# HABduino1_1.net
KiCad netlist of a schematic drawn in EAGLE
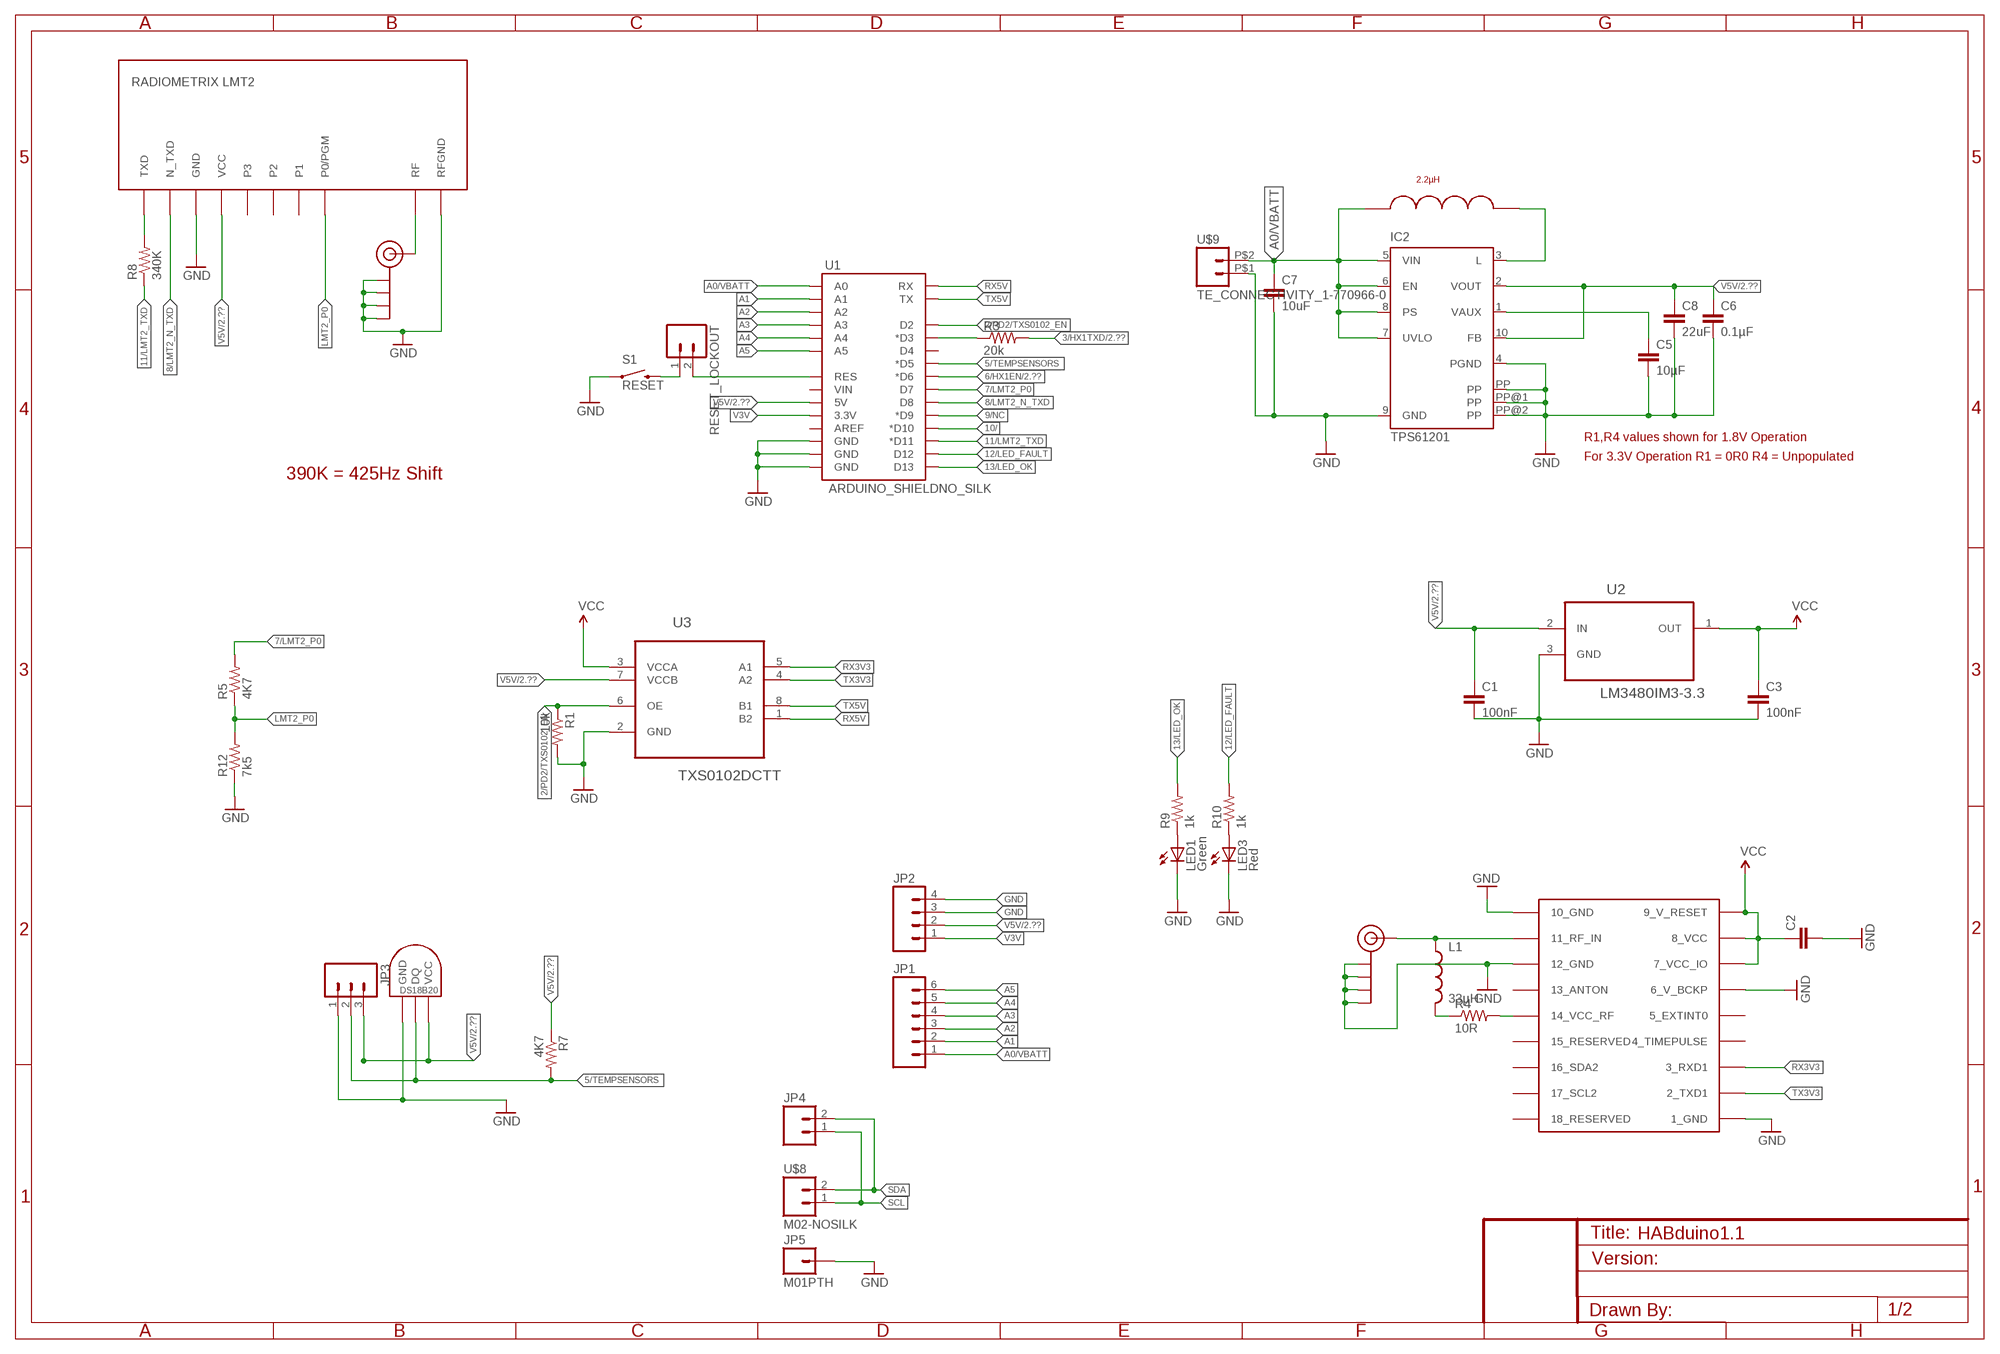
[diagram p0: schematic, sheet 1]
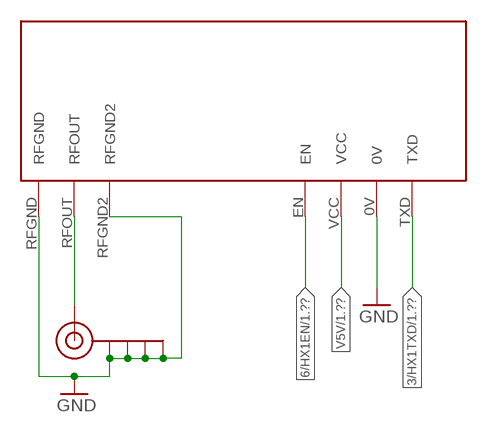
[diagram p1: schematic, sheet 2]

(export (version "E")
  (design (tool "Eeschema 10.0.6"))
  (components
    (comp (ref "J$3")
      (value "SMA_EDGE")
      (footprint "eagle-import:SMA-EDGE")
      (libsource (lib "eagle-import") (part "SMA_EDGE"))
    )
    (comp (ref "U$7")
      (value "RADIOMETRIX-HX1")
      (footprint "eagle-import:RADIOMETRIX-HX1")
      (libsource (lib "eagle-import") (part "RADIOMETRIX-HX1"))
    )
    (comp (ref "C1")
      (value "100nF")
      (footprint "eagle-import:0603-CAP")
      (libsource (lib "eagle-import") (part "CAP0603-CAP"))
    )
    (comp (ref "C2")
      (value "CAP0603-CAP")
      (footprint "eagle-import:0603-CAP")
      (libsource (lib "eagle-import") (part "CAP0603-CAP"))
    )
    (comp (ref "C3")
      (value "100nF")
      (footprint "eagle-import:0603-CAP")
      (libsource (lib "eagle-import") (part "CAP0603-CAP"))
    )
    (comp (ref "C5")
      (value "10µF")
      (footprint "eagle-import:0603-CAP")
      (libsource (lib "eagle-import") (part "CAP0603-CAP"))
    )
    (comp (ref "C6")
      (value "0.1µF")
      (footprint "eagle-import:0603-CAP")
      (libsource (lib "eagle-import") (part "CAP0603-CAP"))
    )
    (comp (ref "C7")
      (value "10uF")
      (footprint "eagle-import:1206")
      (libsource (lib "eagle-import") (part "CAP1206"))
    )
    (comp (ref "C8")
      (value "22uF")
      (footprint "eagle-import:1206")
      (libsource (lib "eagle-import") (part "CAP1206"))
    )
    (comp (ref "IC2")
      (value "TPS61201")
      (footprint "eagle-import:S-PDSO-N10")
      (fields (field (name "MPN") "TPS61201DRCT"))
      (libsource (lib "eagle-import") (part "TPS61201"))
    )
    (comp (ref "J$1")
      (value "SMA_EDGE")
      (footprint "eagle-import:SMA-EDGE")
      (libsource (lib "eagle-import") (part "SMA_EDGE"))
    )
    (comp (ref "J$2")
      (value "SMA_EDGE")
      (footprint "eagle-import:SMA-EDGE")
      (libsource (lib "eagle-import") (part "SMA_EDGE"))
    )
    (comp (ref "JP1")
      (value "M06SIP")
      (footprint "eagle-import:1X06")
      (libsource (lib "eagle-import") (part "M06SIP"))
    )
    (comp (ref "JP2")
      (value "M04PTH")
      (footprint "eagle-import:1X04")
      (libsource (lib "eagle-import") (part "M04PTH"))
    )
    (comp (ref "JP3")
      (value "M03PTH")
      (footprint "eagle-import:1X03")
      (libsource (lib "eagle-import") (part "M03PTH"))
    )
    (comp (ref "JP4")
      (value "M02PTH")
      (footprint "eagle-import:1X02")
      (libsource (lib "eagle-import") (part "M02PTH"))
    )
    (comp (ref "JP5")
      (value "M01PTH")
      (footprint "eagle-import:1X01")
      (libsource (lib "eagle-import") (part "M01PTH"))
    )
    (comp (ref "L1")
      (value "33µH")
      (footprint "eagle-import:0603")
      (libsource (lib "eagle-import") (part "INDUCTOR0603"))
    )
    (comp (ref "LED1")
      (value "Green")
      (footprint "eagle-import:LED-0603")
      (libsource (lib "eagle-import") (part "LED0603"))
    )
    (comp (ref "LED3")
      (value "Red")
      (footprint "eagle-import:LED-0603")
      (libsource (lib "eagle-import") (part "LED0603"))
    )
    (comp (ref "R1")
      (value "10k")
      (footprint "eagle-import:0603-RES")
      (libsource (lib "eagle-import") (part "RESISTOR0603-RES"))
    )
    (comp (ref "R3")
      (value "20k")
      (footprint "eagle-import:0603-RES")
      (libsource (lib "eagle-import") (part "RESISTOR0603-RES"))
    )
    (comp (ref "R4")
      (value "10R")
      (footprint "eagle-import:0603-RES")
      (libsource (lib "eagle-import") (part "RESISTOR0603-RES"))
    )
    (comp (ref "R5")
      (value "4K7")
      (footprint "eagle-import:0603-RES")
      (libsource (lib "eagle-import") (part "RESISTOR0603-RES"))
    )
    (comp (ref "R7")
      (value "4K7")
      (footprint "eagle-import:0603-RES")
      (libsource (lib "eagle-import") (part "RESISTOR0603-RES"))
    )
    (comp (ref "R8")
      (value "340K")
      (footprint "eagle-import:0603-RES")
      (libsource (lib "eagle-import") (part "RESISTOR0603-RES"))
    )
    (comp (ref "R9")
      (value "1k")
      (footprint "eagle-import:0603-RES")
      (libsource (lib "eagle-import") (part "RESISTOR0603-RES"))
    )
    (comp (ref "R10")
      (value "1k")
      (footprint "eagle-import:0603-RES")
      (libsource (lib "eagle-import") (part "RESISTOR0603-RES"))
    )
    (comp (ref "R12")
      (value "7k5")
      (footprint "eagle-import:0603-RES")
      (libsource (lib "eagle-import") (part "RESISTOR0603-RES"))
    )
    (comp (ref "RESET_LOCKOUT")
      (value "M02PTH")
      (footprint "eagle-import:1X02")
      (libsource (lib "eagle-import") (part "M02PTH"))
    )
    (comp (ref "S1")
      (value "RESET")
      (footprint "eagle-import:TACTILE_SWITCH_TALL")
      (libsource (lib "eagle-import") (part "SWITCH-MOMENTARY-2"))
    )
    (comp (ref "TEMPINT")
      (value "DS1821")
      (footprint "eagle-import:DS1820")
      (libsource (lib "eagle-import") (part "DS1820TO92"))
    )
    (comp (ref "U$1")
      (value "UBLOX_MAX-6")
      (footprint "eagle-import:UBLOX_MAX-6")
      (libsource (lib "eagle-import") (part "UBLOX_MAX-6"))
    )
    (comp (ref "U$2")
      (value "RADIOMETRIX_LMT2")
      (footprint "eagle-import:RADIOMETRIX-LMT2")
      (libsource (lib "eagle-import") (part "RADIOMETRIX_LMT2"))
    )
    (comp (ref "U$8")
      (value "M02-NOSILK")
      (footprint "eagle-import:M02-NOSILK")
      (libsource (lib "eagle-import") (part "M02-NOSILK"))
    )
    (comp (ref "U$9")
      (value "TE_CONNECTIVITY_1-770966-0")
      (footprint "eagle-import:TE_CONNECTIVITY_1-770966-0")
      (libsource (lib "eagle-import") (part "TE_CONNECTIVITY_1-770966-0"))
    )
    (comp (ref "U$10")
      (value "2.2µH")
      (footprint "eagle-import:COILCRAFT_LPS4018")
      (libsource (lib "eagle-import") (part "COILCRAFT_LPS4018"))
    )
    (comp (ref "U1")
      (value "ARDUINO_SHIELDNO_SILK")
      (footprint "eagle-import:DUEMILANOVE_VIAS")
      (libsource (lib "eagle-import") (part "ARDUINO_SHIELDNO_SILK"))
    )
    (comp (ref "U2")
      (value "LM3480IM3-3.3")
      (footprint "eagle-import:SOT95P251X112-3N")
      (libsource (lib "eagle-import") (part "LM3480IM3-3.3"))
    )
    (comp (ref "U3")
      (value "TXS0102DCTT")
      (footprint "eagle-import:SOP65P400X130-8N")
      (libsource (lib "eagle-import") (part "TXS0102DCTT"))
    )
  )
  (nets
    (net (code "1") (name "2{slash}PD2{slash}TXS0102_EN") (class "Default")
      (node (ref "R1") (pin "1") (pinfunction "1_1") (pintype "passive"))
      (node (ref "U1") (pin "D2") (pinfunction "D2_D2") (pintype "bidirectional"))
      (node (ref "U3") (pin "6") (pinfunction "OE_6") (pintype "input"))
    )
    (net (code "2") (name "3{slash}HX1TXD") (class "Default")
      (node (ref "R3") (pin "2") (pinfunction "2_2") (pintype "passive"))
      (node (ref "U$7") (pin "TXD") (pinfunction "TXD_TXD") (pintype "bidirectional"))
    )
    (net (code "3") (name "5{slash}TEMPSENSORS") (class "Default")
      (node (ref "JP3") (pin "2") (pinfunction "2_2") (pintype "passive"))
      (node (ref "R7") (pin "2") (pinfunction "2_2") (pintype "passive"))
      (node (ref "TEMPINT") (pin "DQ") (pinfunction "DQ_DQ") (pintype "bidirectional"))
      (node (ref "U1") (pin "D5") (pinfunction "*D5_D5") (pintype "bidirectional"))
    )
    (net (code "4") (name "6{slash}HX1EN") (class "Default")
      (node (ref "U$7") (pin "EN") (pinfunction "EN_EN") (pintype "bidirectional"))
      (node (ref "U1") (pin "D6") (pinfunction "*D6_D6") (pintype "bidirectional"))
    )
    (net (code "5") (name "7{slash}LMT2_P0") (class "Default")
      (node (ref "R5") (pin "2") (pinfunction "2_2") (pintype "passive"))
      (node (ref "U1") (pin "D7") (pinfunction "D7_D7") (pintype "bidirectional"))
    )
    (net (code "6") (name "8{slash}LMT2_N_TXD") (class "Default")
      (node (ref "U$2") (pin "N_TXE") (pinfunction "N_TXD_N_TXE") (pintype "bidirectional"))
      (node (ref "U1") (pin "D8") (pinfunction "D8_D8") (pintype "bidirectional"))
    )
    (net (code "7") (name "9{slash}NC") (class "Default")
      (node (ref "U1") (pin "D9") (pinfunction "*D9_D9") (pintype "bidirectional"))
    )
    (net (code "8") (name "10{slash}") (class "Default")
      (node (ref "U1") (pin "D10") (pinfunction "*D10_D10") (pintype "bidirectional"))
    )
    (net (code "9") (name "11{slash}LMT2_TXD") (class "Default")
      (node (ref "R8") (pin "1") (pinfunction "1_1") (pintype "passive"))
      (node (ref "U1") (pin "D11") (pinfunction "*D11_D11") (pintype "bidirectional"))
    )
    (net (code "10") (name "12{slash}LED_FAULT") (class "Default")
      (node (ref "R10") (pin "2") (pinfunction "2_2") (pintype "passive"))
      (node (ref "U1") (pin "D12") (pinfunction "D12_D12") (pintype "bidirectional"))
    )
    (net (code "11") (name "13{slash}LED_OK") (class "Default")
      (node (ref "R9") (pin "2") (pinfunction "2_2") (pintype "passive"))
      (node (ref "U1") (pin "D13") (pinfunction "D13_D13") (pintype "bidirectional"))
    )
    (net (code "12") (name "A0{slash}VBATT") (class "Default")
      (node (ref "C7") (pin "1") (pinfunction "1_1") (pintype "passive"))
      (node (ref "IC2") (pin "5") (pinfunction "VIN_5") (pintype "input"))
      (node (ref "IC2") (pin "6") (pinfunction "EN_6") (pintype "input"))
      (node (ref "IC2") (pin "7") (pinfunction "UVLO_7") (pintype "input"))
      (node (ref "IC2") (pin "8") (pinfunction "PS_8") (pintype "input"))
      (node (ref "JP1") (pin "1") (pinfunction "1_1") (pintype "passive"))
      (node (ref "U$10") (pin "P$1") (pinfunction "P$1_P$1") (pintype "bidirectional"))
      (node (ref "U$9") (pin "P$2") (pinfunction "2_P$2") (pintype "passive"))
      (node (ref "U1") (pin "A0") (pinfunction "A0_A0") (pintype "bidirectional"))
    )
    (net (code "13") (name "A1") (class "Default")
      (node (ref "JP1") (pin "2") (pinfunction "2_2") (pintype "passive"))
      (node (ref "U1") (pin "A1") (pinfunction "A1_A1") (pintype "bidirectional"))
    )
    (net (code "14") (name "A2") (class "Default")
      (node (ref "JP1") (pin "3") (pinfunction "3_3") (pintype "passive"))
      (node (ref "U1") (pin "A2") (pinfunction "A2_A2") (pintype "bidirectional"))
    )
    (net (code "15") (name "A3") (class "Default")
      (node (ref "JP1") (pin "4") (pinfunction "4_4") (pintype "passive"))
      (node (ref "U1") (pin "A3") (pinfunction "A3_A3") (pintype "bidirectional"))
    )
    (net (code "16") (name "A4") (class "Default")
      (node (ref "JP1") (pin "5") (pinfunction "5_5") (pintype "passive"))
      (node (ref "U1") (pin "A4") (pinfunction "A4_A4") (pintype "bidirectional"))
    )
    (net (code "17") (name "A5") (class "Default")
      (node (ref "JP1") (pin "6") (pinfunction "6_6") (pintype "passive"))
      (node (ref "U1") (pin "A5") (pinfunction "A5_A5") (pintype "bidirectional"))
    )
    (net (code "18") (name "GND") (class "Default")
      (node (ref "C1") (pin "2") (pinfunction "2_2") (pintype "passive"))
      (node (ref "C2") (pin "2") (pinfunction "2_2") (pintype "passive"))
      (node (ref "C3") (pin "2") (pinfunction "2_2") (pintype "passive"))
      (node (ref "C5") (pin "2") (pinfunction "2_2") (pintype "passive"))
      (node (ref "C6") (pin "2") (pinfunction "2_2") (pintype "passive"))
      (node (ref "C7") (pin "2") (pinfunction "2_2") (pintype "passive"))
      (node (ref "C8") (pin "2") (pinfunction "2_2") (pintype "passive"))
      (node (ref "IC2") (pin "4") (pinfunction "PGND_4") (pintype "power_in"))
      (node (ref "IC2") (pin "9") (pinfunction "GND_9") (pintype "power_in"))
      (node (ref "IC2") (pin "PP") (pinfunction "PP_PP") (pintype "power_in"))
      (node (ref "IC2") (pin "PP@1") (pinfunction "PP_PP@1") (pintype "power_in"))
      (node (ref "IC2") (pin "PP@2") (pinfunction "PP_PP@2") (pintype "power_in"))
      (node (ref "J$1") (pin "GND@0") (pinfunction "GND_GND@0") (pintype "bidirectional"))
      (node (ref "J$1") (pin "GND@1") (pinfunction "GND_GND@1") (pintype "bidirectional"))
      (node (ref "J$1") (pin "GND@2") (pinfunction "GND_GND@2") (pintype "bidirectional"))
      (node (ref "J$1") (pin "GND@3") (pinfunction "GND_GND@3") (pintype "bidirectional"))
      (node (ref "J$2") (pin "GND@0") (pinfunction "GND_GND@0") (pintype "bidirectional"))
      (node (ref "J$2") (pin "GND@1") (pinfunction "GND_GND@1") (pintype "bidirectional"))
      (node (ref "J$2") (pin "GND@2") (pinfunction "GND_GND@2") (pintype "bidirectional"))
      (node (ref "J$2") (pin "GND@3") (pinfunction "GND_GND@3") (pintype "bidirectional"))
      (node (ref "J$3") (pin "GND@0") (pinfunction "GND_GND@0") (pintype "bidirectional"))
      (node (ref "J$3") (pin "GND@1") (pinfunction "GND_GND@1") (pintype "bidirectional"))
      (node (ref "J$3") (pin "GND@2") (pinfunction "GND_GND@2") (pintype "bidirectional"))
      (node (ref "J$3") (pin "GND@3") (pinfunction "GND_GND@3") (pintype "bidirectional"))
      (node (ref "JP2") (pin "3") (pinfunction "3_3") (pintype "passive"))
      (node (ref "JP2") (pin "4") (pinfunction "4_4") (pintype "passive"))
      (node (ref "JP3") (pin "1") (pinfunction "1_1") (pintype "passive"))
      (node (ref "JP5") (pin "1") (pinfunction "1_1") (pintype "passive"))
      (node (ref "LED1") (pin "C") (pinfunction "C_C") (pintype "passive"))
      (node (ref "LED3") (pin "C") (pinfunction "C_C") (pintype "passive"))
      (node (ref "R1") (pin "2") (pinfunction "2_2") (pintype "passive"))
      (node (ref "R12") (pin "1") (pinfunction "1_1") (pintype "passive"))
      (node (ref "S1") (pin "A2") (pinfunction "1_A2") (pintype "passive"))
      (node (ref "TEMPINT") (pin "GND") (pinfunction "GND_GND") (pintype "power_in"))
      (node (ref "U$1") (pin "10_GND") (pinfunction "10_GND_10_GND") (pintype "bidirectional"))
      (node (ref "U$1") (pin "12_GND") (pinfunction "12_GND_12_GND") (pintype "bidirectional"))
      (node (ref "U$1") (pin "1_GND") (pinfunction "1_GND_1_GND") (pintype "bidirectional"))
      (node (ref "U$1") (pin "6_V_BCKP") (pinfunction "6_V_BCKP_6_V_BCKP") (pintype "bidirectional"))
      (node (ref "U$2") (pin "GND") (pinfunction "GND_GND") (pintype "power_in"))
      (node (ref "U$2") (pin "RFGND") (pinfunction "RFGND_RFGND") (pintype "bidirectional"))
      (node (ref "U$7") (pin "0V") (pinfunction "0V_0V") (pintype "bidirectional"))
      (node (ref "U$7") (pin "RFGND") (pinfunction "RFGND_RFGND") (pintype "bidirectional"))
      (node (ref "U$7") (pin "RFGND2") (pinfunction "RFGND2_RFGND2") (pintype "bidirectional"))
      (node (ref "U$9") (pin "P$1") (pinfunction "1_P$1") (pintype "passive"))
      (node (ref "U1") (pin "GND@0") (pinfunction "GND_GND@0") (pintype "bidirectional"))
      (node (ref "U1") (pin "GND@1") (pinfunction "GND_GND@1") (pintype "bidirectional"))
      (node (ref "U1") (pin "GND@2") (pinfunction "GND_GND@2") (pintype "bidirectional"))
      (node (ref "U2") (pin "3") (pinfunction "GND_3") (pintype "passive"))
      (node (ref "U3") (pin "2") (pinfunction "GND_2") (pintype "passive"))
    )
    (net (code "19") (name "LMT2_P0") (class "Default")
      (node (ref "R12") (pin "2") (pinfunction "2_2") (pintype "passive"))
      (node (ref "R5") (pin "1") (pinfunction "1_1") (pintype "passive"))
      (node (ref "U$2") (pin "P0/PGM") (pinfunction "P0/PGM_P0/PGM") (pintype "bidirectional"))
    )
    (net (code "20") (name "Net-(IC2-L)") (class "Default")
      (node (ref "IC2") (pin "3") (pinfunction "L_3") (pintype "input"))
      (node (ref "U$10") (pin "P$2") (pinfunction "P$2_P$2") (pintype "bidirectional"))
    )
    (net (code "21") (name "Net-(IC2-VAUX)") (class "Default")
      (node (ref "C5") (pin "1") (pinfunction "1_1") (pintype "passive"))
      (node (ref "IC2") (pin "1") (pinfunction "VAUX_1") (pintype "bidirectional"))
    )
    (net (code "22") (name "Net-(J$1-SIGNAL)") (class "Default")
      (node (ref "J$1") (pin "SIG") (pinfunction "SIGNAL_SIG") (pintype "bidirectional"))
      (node (ref "U$2") (pin "RF") (pinfunction "RF_RF") (pintype "bidirectional"))
    )
    (net (code "23") (name "Net-(J$2-SIGNAL)") (class "Default")
      (node (ref "J$2") (pin "SIG") (pinfunction "SIGNAL_SIG") (pintype "bidirectional"))
      (node (ref "L1") (pin "1") (pinfunction "1_1") (pintype "passive"))
      (node (ref "U$1") (pin "11_RF_IN") (pinfunction "11_RF_IN_11_RF_IN") (pintype "bidirectional"))
    )
    (net (code "24") (name "Net-(J$3-SIGNAL)") (class "Default")
      (node (ref "J$3") (pin "SIG") (pinfunction "SIGNAL_SIG") (pintype "bidirectional"))
      (node (ref "U$7") (pin "RFOUT") (pinfunction "RFOUT_RFOUT") (pintype "bidirectional"))
    )
    (net (code "25") (name "Net-(L1-Pad2)") (class "Default")
      (node (ref "L1") (pin "2") (pinfunction "2_2") (pintype "passive"))
      (node (ref "R4") (pin "1") (pinfunction "1_1") (pintype "passive"))
    )
    (net (code "26") (name "Net-(LED1-PadA)") (class "Default")
      (node (ref "LED1") (pin "A") (pinfunction "A_A") (pintype "passive"))
      (node (ref "R9") (pin "1") (pinfunction "1_1") (pintype "passive"))
    )
    (net (code "27") (name "Net-(LED3-PadA)") (class "Default")
      (node (ref "LED3") (pin "A") (pinfunction "A_A") (pintype "passive"))
      (node (ref "R10") (pin "1") (pinfunction "1_1") (pintype "passive"))
    )
    (net (code "28") (name "Net-(R4-Pad2)") (class "Default")
      (node (ref "R4") (pin "2") (pinfunction "2_2") (pintype "passive"))
      (node (ref "U$1") (pin "14_VCC_RF") (pinfunction "14_VCC_RF_14_VCC_RF") (pintype "bidirectional"))
    )
    (net (code "29") (name "Net-(R8-Pad2)") (class "Default")
      (node (ref "R8") (pin "2") (pinfunction "2_2") (pintype "passive"))
      (node (ref "U$2") (pin "TXD") (pinfunction "TXD_TXD") (pintype "bidirectional"))
    )
    (net (code "30") (name "Net-(RESET_LOCKOUT-Pad2)") (class "Default")
      (node (ref "RESET_LOCKOUT") (pin "2") (pinfunction "2_2") (pintype "passive"))
      (node (ref "U1") (pin "RES") (pinfunction "RES_RES") (pintype "bidirectional"))
    )
    (net (code "31") (name "Net-(S1-2)") (class "Default")
      (node (ref "RESET_LOCKOUT") (pin "1") (pinfunction "1_1") (pintype "passive"))
      (node (ref "S1") (pin "B2") (pinfunction "2_B2") (pintype "passive"))
    )
    (net (code "32") (name "Net-(U1-*D3)") (class "Default")
      (node (ref "R3") (pin "1") (pinfunction "1_1") (pintype "passive"))
      (node (ref "U1") (pin "D3") (pinfunction "*D3_D3") (pintype "bidirectional"))
    )
    (net (code "33") (name "RX3V3") (class "Default")
      (node (ref "U$1") (pin "3_RXD1") (pinfunction "3_RXD1_3_RXD1") (pintype "bidirectional"))
      (node (ref "U3") (pin "5") (pinfunction "A1_5") (pintype "bidirectional"))
    )
    (net (code "34") (name "RX5V") (class "Default")
      (node (ref "U1") (pin "RX") (pinfunction "RX_RX") (pintype "bidirectional"))
      (node (ref "U3") (pin "1") (pinfunction "B2_1") (pintype "bidirectional"))
    )
    (net (code "35") (name "SCL") (class "Default")
      (node (ref "JP4") (pin "1") (pinfunction "1_1") (pintype "passive"))
      (node (ref "U$8") (pin "1") (pinfunction "1_1") (pintype "passive"))
    )
    (net (code "36") (name "SDA") (class "Default")
      (node (ref "JP4") (pin "2") (pinfunction "2_2") (pintype "passive"))
      (node (ref "U$8") (pin "2") (pinfunction "2_2") (pintype "passive"))
    )
    (net (code "37") (name "TX3V3") (class "Default")
      (node (ref "U$1") (pin "2_TXD1") (pinfunction "2_TXD1_2_TXD1") (pintype "bidirectional"))
      (node (ref "U3") (pin "4") (pinfunction "A2_4") (pintype "bidirectional"))
    )
    (net (code "38") (name "TX5V") (class "Default")
      (node (ref "U1") (pin "TX") (pinfunction "TX_TX") (pintype "bidirectional"))
      (node (ref "U3") (pin "8") (pinfunction "B1_8") (pintype "bidirectional"))
    )
    (net (code "39") (name "V3V") (class "Default")
      (node (ref "JP2") (pin "1") (pinfunction "1_1") (pintype "passive"))
      (node (ref "U1") (pin "3.3V") (pinfunction "3.3V_3.3V") (pintype "bidirectional"))
    )
    (net (code "40") (name "V5V") (class "Default")
      (node (ref "C1") (pin "1") (pinfunction "1_1") (pintype "passive"))
      (node (ref "C6") (pin "1") (pinfunction "1_1") (pintype "passive"))
      (node (ref "C8") (pin "1") (pinfunction "1_1") (pintype "passive"))
      (node (ref "IC2") (pin "10") (pinfunction "FB_10") (pintype "input"))
      (node (ref "IC2") (pin "2") (pinfunction "VOUT_2") (pintype "passive"))
      (node (ref "JP2") (pin "2") (pinfunction "2_2") (pintype "passive"))
      (node (ref "JP3") (pin "3") (pinfunction "3_3") (pintype "passive"))
      (node (ref "R7") (pin "1") (pinfunction "1_1") (pintype "passive"))
      (node (ref "TEMPINT") (pin "VDD") (pinfunction "VCC_VDD") (pintype "power_in"))
      (node (ref "U$2") (pin "VCC") (pinfunction "VCC_VCC") (pintype "power_in"))
      (node (ref "U$7") (pin "VCC") (pinfunction "VCC_VCC") (pintype "bidirectional"))
      (node (ref "U1") (pin "5V") (pinfunction "5V_5V") (pintype "bidirectional"))
      (node (ref "U2") (pin "2") (pinfunction "IN_2") (pintype "power_in"))
      (node (ref "U3") (pin "7") (pinfunction "VCCB_7") (pintype "power_in"))
    )
    (net (code "41") (name "VCC") (class "Default")
      (node (ref "C2") (pin "1") (pinfunction "1_1") (pintype "passive"))
      (node (ref "C3") (pin "1") (pinfunction "1_1") (pintype "passive"))
      (node (ref "U$1") (pin "7_VCC_IO") (pinfunction "7_VCC_IO_7_VCC_IO") (pintype "bidirectional"))
      (node (ref "U$1") (pin "8_VCC") (pinfunction "8_VCC_8_VCC") (pintype "bidirectional"))
      (node (ref "U$1") (pin "9_V_RESET") (pinfunction "9_V_RESET_9_V_RESET") (pintype "bidirectional"))
      (node (ref "U2") (pin "1") (pinfunction "OUT_1") (pintype "output"))
      (node (ref "U3") (pin "3") (pinfunction "VCCA_3") (pintype "power_in"))
    )
    (net (code "42") (name "unconnected-(U$1-Pad4_TIMEPULSE)") (class "Default")
      (node (ref "U$1") (pin "4_TIMEPULSE") (pinfunction "4_TIMEPULSE_4_TIMEPULSE") (pintype "bidirectional"))
    )
    (net (code "43") (name "unconnected-(U$1-Pad5_EXTINT0)") (class "Default")
      (node (ref "U$1") (pin "5_EXTINT0") (pinfunction "5_EXTINT0_5_EXTINT0") (pintype "bidirectional"))
    )
    (net (code "44") (name "unconnected-(U$1-Pad13_ANTON)") (class "Default")
      (node (ref "U$1") (pin "13_ANTON") (pinfunction "13_ANTON_13_ANTON") (pintype "bidirectional"))
    )
    (net (code "45") (name "unconnected-(U$1-Pad15_RESERVED)") (class "Default")
      (node (ref "U$1") (pin "15_RESERVED") (pinfunction "15_RESERVED_15_RESERVED") (pintype "bidirectional"))
    )
    (net (code "46") (name "unconnected-(U$1-Pad16_SDA2)") (class "Default")
      (node (ref "U$1") (pin "16_SDA2") (pinfunction "16_SDA2_16_SDA2") (pintype "bidirectional"))
    )
    (net (code "47") (name "unconnected-(U$1-Pad17_SCL2)") (class "Default")
      (node (ref "U$1") (pin "17_SCL2") (pinfunction "17_SCL2_17_SCL2") (pintype "bidirectional"))
    )
    (net (code "48") (name "unconnected-(U$1-Pad18_RESERVED)") (class "Default")
      (node (ref "U$1") (pin "18_RESERVED") (pinfunction "18_RESERVED_18_RESERVED") (pintype "bidirectional"))
    )
    (net (code "49") (name "unconnected-(U$2-PadP1)") (class "Default")
      (node (ref "U$2") (pin "P1") (pinfunction "P1_P1") (pintype "bidirectional"))
    )
    (net (code "50") (name "unconnected-(U$2-PadP2)") (class "Default")
      (node (ref "U$2") (pin "P2") (pinfunction "P2_P2") (pintype "bidirectional"))
    )
    (net (code "51") (name "unconnected-(U$2-PadP3)") (class "Default")
      (node (ref "U$2") (pin "P3") (pinfunction "P3_P3") (pintype "bidirectional"))
    )
    (net (code "52") (name "unconnected-(U1-PadAREF)") (class "Default")
      (node (ref "U1") (pin "AREF") (pinfunction "AREF_AREF") (pintype "bidirectional"))
    )
    (net (code "53") (name "unconnected-(U1-PadD4)") (class "Default")
      (node (ref "U1") (pin "D4") (pinfunction "D4_D4") (pintype "bidirectional"))
    )
    (net (code "54") (name "unconnected-(U1-PadVIN)") (class "Default")
      (node (ref "U1") (pin "VIN") (pinfunction "VIN_VIN") (pintype "bidirectional"))
    )
  )
)
